# sx-wdec1-2313.net
KiCad netlist of a schematic drawn in EAGLE
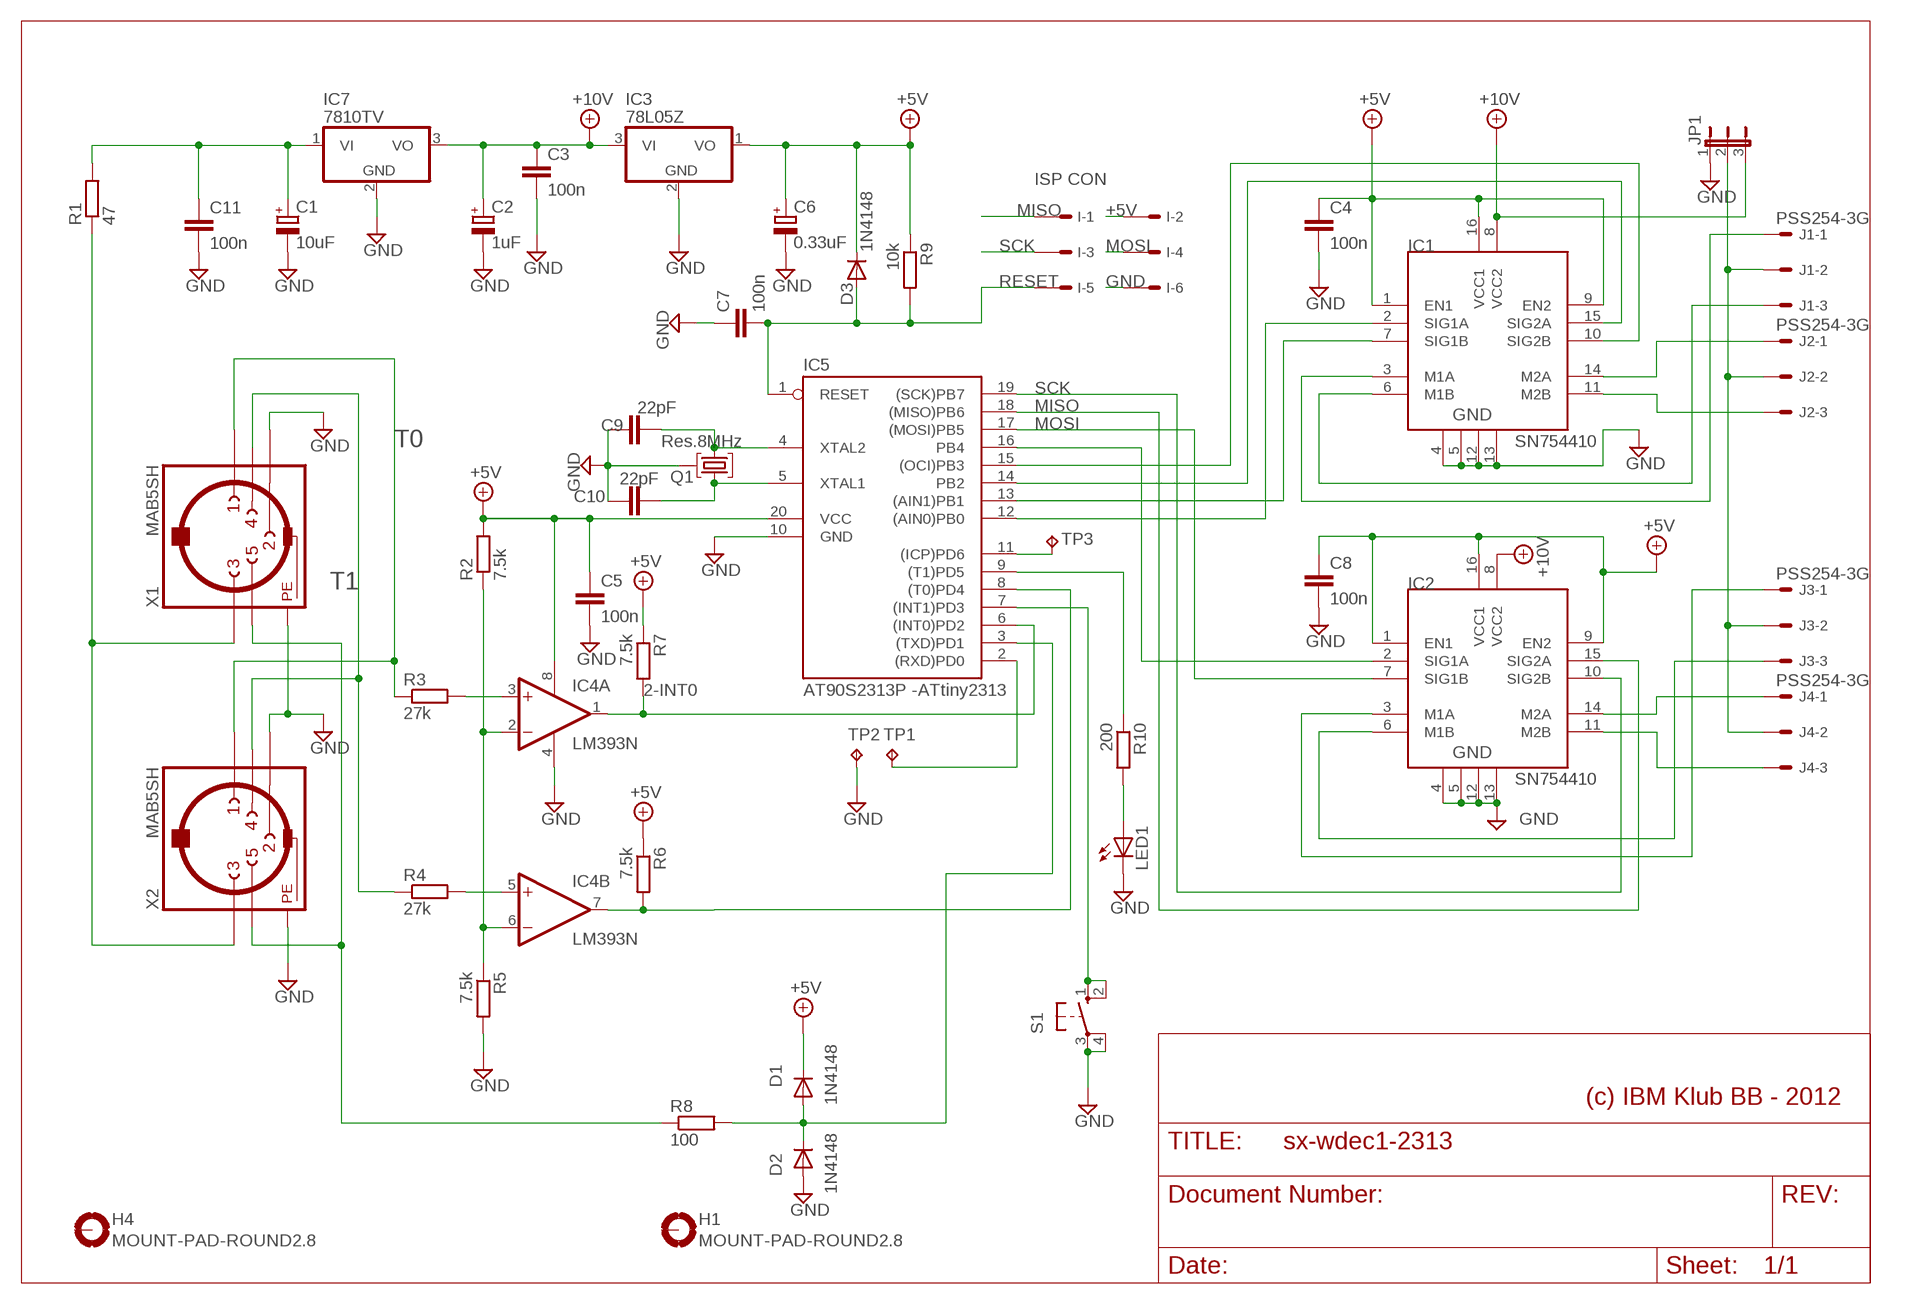
[diagram p0: schematic, sheet 1]

(export (version "E")
  (design (tool "Eeschema 10.0.6"))
  (components
    (comp (ref "C1")
      (value "10uF")
      (footprint "eagle-import:E2,5-7")
      (libsource (lib "eagle-import") (part "CPOL-EUE2.5-7"))
    )
    (comp (ref "C2")
      (value "1uF")
      (footprint "eagle-import:E2,5-7")
      (libsource (lib "eagle-import") (part "CPOL-EUE2.5-7"))
    )
    (comp (ref "C3")
      (value "100n")
      (footprint "eagle-import:C050-025X075")
      (libsource (lib "eagle-import") (part "C-EU050-025X075"))
    )
    (comp (ref "C4")
      (value "100n")
      (footprint "eagle-import:C050-025X075")
      (libsource (lib "eagle-import") (part "C-EU050-025X075"))
    )
    (comp (ref "C5")
      (value "100n")
      (footprint "eagle-import:C050-025X075")
      (libsource (lib "eagle-import") (part "C-EU050-025X075"))
    )
    (comp (ref "C6")
      (value "0.33uF")
      (footprint "eagle-import:E2,5-5")
      (libsource (lib "eagle-import") (part "CPOL-EUE2.5-5"))
    )
    (comp (ref "C7")
      (value "100n")
      (footprint "eagle-import:C050-025X075")
      (libsource (lib "eagle-import") (part "C-EU050-025X075"))
    )
    (comp (ref "C8")
      (value "100n")
      (footprint "eagle-import:C050-025X075")
      (libsource (lib "eagle-import") (part "C-EU050-025X075"))
    )
    (comp (ref "C9")
      (value "22pF")
      (footprint "eagle-import:C025-025X050")
      (libsource (lib "eagle-import") (part "C-EU025-025X050"))
    )
    (comp (ref "C10")
      (value "22pF")
      (footprint "eagle-import:C025-025X050")
      (libsource (lib "eagle-import") (part "C-EU025-025X050"))
    )
    (comp (ref "C11")
      (value "100n")
      (footprint "eagle-import:C050-025X075")
      (libsource (lib "eagle-import") (part "C-EU050-025X075"))
    )
    (comp (ref "D1")
      (value "1N4148")
      (footprint "eagle-import:DO35-7")
      (libsource (lib "eagle-import") (part "1N4148DO35-7"))
    )
    (comp (ref "D2")
      (value "1N4148")
      (footprint "eagle-import:DO35-7")
      (libsource (lib "eagle-import") (part "1N4148DO35-7"))
    )
    (comp (ref "D3")
      (value "1N4148")
      (footprint "eagle-import:DO35-7")
      (libsource (lib "eagle-import") (part "1N4148DO35-7"))
    )
    (comp (ref "H1")
      (value "MOUNT-PAD-ROUND2.8")
      (footprint "eagle-import:2,8-PAD")
      (libsource (lib "eagle-import") (part "MOUNT-PAD-ROUND2.8"))
    )
    (comp (ref "H4")
      (value "MOUNT-PAD-ROUND2.8")
      (footprint "eagle-import:2,8-PAD")
      (libsource (lib "eagle-import") (part "MOUNT-PAD-ROUND2.8"))
    )
    (comp (ref "I")
      (value "ISP CON")
      (footprint "eagle-import:057-006-1")
      (libsource (lib "eagle-import") (part "057-006-1"))
    )
    (comp (ref "IC1")
      (value "SN754410")
      (footprint "eagle-import:DIP16")
      (libsource (lib "eagle-import") (part "SN754410"))
    )
    (comp (ref "IC2")
      (value "SN754410")
      (footprint "eagle-import:DIP16")
      (libsource (lib "eagle-import") (part "SN754410"))
    )
    (comp (ref "IC3")
      (value "78L05Z")
      (footprint "eagle-import:TO92")
      (libsource (lib "eagle-import") (part "78ZL05"))
    )
    (comp (ref "IC4")
      (value "LM393N")
      (footprint "eagle-import:DIL08")
      (libsource (lib "eagle-import") (part "LM393N"))
    )
    (comp (ref "IC5")
      (value "AT90S2313P -ATtiny2313")
      (footprint "eagle-import:DIL20")
      (libsource (lib "eagle-import") (part "AT90S2313P"))
    )
    (comp (ref "IC7")
      (value "7810TV")
      (footprint "eagle-import:TO220V")
      (libsource (lib "eagle-import") (part "78TV12"))
    )
    (comp (ref "J1")
      (value "PSS254-3G")
      (footprint "eagle-import:6410-03")
      (libsource (lib "eagle-import") (part "22-?-0327-2031"))
    )
    (comp (ref "J2")
      (value "PSS254-3G")
      (footprint "eagle-import:6410-03")
      (libsource (lib "eagle-import") (part "22-?-0327-2031"))
    )
    (comp (ref "J3")
      (value "PSS254-3G")
      (footprint "eagle-import:6410-03")
      (libsource (lib "eagle-import") (part "22-?-0327-2031"))
    )
    (comp (ref "J4")
      (value "PSS254-3G")
      (footprint "eagle-import:6410-03")
      (libsource (lib "eagle-import") (part "22-?-0327-2031"))
    )
    (comp (ref "JP1")
      (value "JP2E")
      (footprint "eagle-import:JP2")
      (libsource (lib "eagle-import") (part "JP2E"))
    )
    (comp (ref "LED1")
      (value "LED3MM")
      (footprint "eagle-import:LED3MM")
      (libsource (lib "eagle-import") (part "LED3MM"))
    )
    (comp (ref "Q1")
      (value "Res.8MHz")
      (footprint "eagle-import:HC49U")
      (fields (field (name "OC_FARNELL") "unknown") (field (name "OC_NEWARK") "unknown"))
      (libsource (lib "eagle-import") (part "ECSECS-10.7-15A"))
    )
    (comp (ref "R1")
      (value "47")
      (footprint "eagle-import:0207_12")
      (libsource (lib "eagle-import") (part "R-EU_0207/12"))
    )
    (comp (ref "R2")
      (value "7.5k")
      (footprint "eagle-import:0207_10")
      (libsource (lib "eagle-import") (part "R-EU_0207/10"))
    )
    (comp (ref "R3")
      (value "27k")
      (footprint "eagle-import:0207_10")
      (libsource (lib "eagle-import") (part "R-EU_0207/10"))
    )
    (comp (ref "R4")
      (value "27k")
      (footprint "eagle-import:0207_10")
      (libsource (lib "eagle-import") (part "R-EU_0207/10"))
    )
    (comp (ref "R5")
      (value "7.5k")
      (footprint "eagle-import:0207_10")
      (libsource (lib "eagle-import") (part "R-EU_0207/10"))
    )
    (comp (ref "R6")
      (value "7.5k")
      (footprint "eagle-import:0207_10")
      (libsource (lib "eagle-import") (part "R-EU_0207/10"))
    )
    (comp (ref "R7")
      (value "7.5k")
      (footprint "eagle-import:0207_10")
      (libsource (lib "eagle-import") (part "R-EU_0207/10"))
    )
    (comp (ref "R8")
      (value "100")
      (footprint "eagle-import:0207_10")
      (libsource (lib "eagle-import") (part "R-EU_0207/10"))
    )
    (comp (ref "R9")
      (value "10k")
      (footprint "eagle-import:0207_10")
      (libsource (lib "eagle-import") (part "R-EU_0207/10"))
    )
    (comp (ref "R10")
      (value "200")
      (footprint "eagle-import:0207_10")
      (libsource (lib "eagle-import") (part "R-EU_0207/10"))
    )
    (comp (ref "S1")
      (value "10-XX")
      (footprint "eagle-import:B3F-10XX")
      (fields (field (name "MPN") "B3F-1000"))
      (libsource (lib "eagle-import") (part "10-XX"))
    )
    (comp (ref "TP1")
      (value "TPPAD1-13")
      (footprint "eagle-import:P1-13")
      (libsource (lib "eagle-import") (part "TPPAD1-13"))
    )
    (comp (ref "TP2")
      (value "TPPAD1-13")
      (footprint "eagle-import:P1-13")
      (libsource (lib "eagle-import") (part "TPPAD1-13"))
    )
    (comp (ref "TP3")
      (value "TPPAD1-13")
      (footprint "eagle-import:P1-13")
      (libsource (lib "eagle-import") (part "TPPAD1-13"))
    )
    (comp (ref "X1")
      (value "MAB5SH")
      (footprint "eagle-import:MAB5SH")
      (libsource (lib "eagle-import") (part "MAB5SH"))
    )
    (comp (ref "X2")
      (value "MAB5SH")
      (footprint "eagle-import:MAB5SH")
      (libsource (lib "eagle-import") (part "MAB5SH"))
    )
  )
  (nets
    (net (code "1") (name "+5V") (class "Default")
      (node (ref "C4") (pin "1") (pinfunction "1_1") (pintype "passive"))
      (node (ref "C5") (pin "1") (pinfunction "1_1") (pintype "passive"))
      (node (ref "C6") (pin "+") (pinfunction "+_+") (pintype "passive"))
      (node (ref "C8") (pin "1") (pinfunction "1_1") (pintype "passive"))
      (node (ref "D1") (pin "C") (pinfunction "C_C") (pintype "passive"))
      (node (ref "D3") (pin "C") (pinfunction "C_C") (pintype "passive"))
      (node (ref "I") (pin "2") (pinfunction "S_2") (pintype "passive"))
      (node (ref "IC1") (pin "1") (pinfunction "EN1_1") (pintype "bidirectional"))
      (node (ref "IC1") (pin "16") (pinfunction "VCC1_16") (pintype "power_in"))
      (node (ref "IC1") (pin "9") (pinfunction "EN2_9") (pintype "bidirectional"))
      (node (ref "IC2") (pin "1") (pinfunction "EN1_1") (pintype "bidirectional"))
      (node (ref "IC2") (pin "16") (pinfunction "VCC1_16") (pintype "power_in"))
      (node (ref "IC2") (pin "9") (pinfunction "EN2_9") (pintype "bidirectional"))
      (node (ref "IC3") (pin "1") (pinfunction "VO_1") (pintype "passive"))
      (node (ref "IC4") (pin "8") (pinfunction "V+_8") (pintype "power_in"))
      (node (ref "IC5") (pin "20") (pinfunction "VCC_20") (pintype "power_in"))
      (node (ref "R2") (pin "2") (pinfunction "2_2") (pintype "passive"))
      (node (ref "R6") (pin "1") (pinfunction "1_1") (pintype "passive"))
      (node (ref "R7") (pin "1") (pinfunction "1_1") (pintype "passive"))
      (node (ref "R9") (pin "1") (pinfunction "1_1") (pintype "passive"))
    )
    (net (code "2") (name "+10V") (class "Default")
      (node (ref "C2") (pin "+") (pinfunction "+_+") (pintype "passive"))
      (node (ref "C3") (pin "1") (pinfunction "1_1") (pintype "passive"))
      (node (ref "IC1") (pin "8") (pinfunction "VCC2_8") (pintype "power_in"))
      (node (ref "IC2") (pin "8") (pinfunction "VCC2_8") (pintype "power_in"))
      (node (ref "IC3") (pin "3") (pinfunction "VI_3") (pintype "input"))
      (node (ref "IC7") (pin "3") (pinfunction "VO_3") (pintype "passive"))
      (node (ref "JP1") (pin "3") (pinfunction "3_3") (pintype "passive"))
    )
    (net (code "3") (name "/2-INT0") (class "Default")
      (node (ref "IC4") (pin "1") (pinfunction "OUT_1") (pintype "output"))
      (node (ref "IC5") (pin "6") (pinfunction "(INT0)PD2_6") (pintype "bidirectional"))
      (node (ref "R7") (pin "2") (pinfunction "2_2") (pintype "passive"))
    )
    (net (code "4") (name "/MISO") (class "Default")
      (node (ref "I") (pin "1") (pinfunction "S_1") (pintype "passive"))
      (node (ref "IC2") (pin "15") (pinfunction "SIG2A_15") (pintype "bidirectional"))
      (node (ref "IC5") (pin "18") (pinfunction "(MISO)PB6_18") (pintype "bidirectional"))
    )
    (net (code "5") (name "/MOSI") (class "Default")
      (node (ref "I") (pin "4") (pinfunction "S_4") (pintype "passive"))
      (node (ref "IC2") (pin "7") (pinfunction "SIG1B_7") (pintype "bidirectional"))
      (node (ref "IC5") (pin "17") (pinfunction "(MOSI)PB5_17") (pintype "bidirectional"))
    )
    (net (code "6") (name "/RESET") (class "Default")
      (node (ref "C7") (pin "2") (pinfunction "2_2") (pintype "passive"))
      (node (ref "D3") (pin "A") (pinfunction "A_A") (pintype "passive"))
      (node (ref "I") (pin "5") (pinfunction "S_5") (pintype "passive"))
      (node (ref "IC5") (pin "1") (pinfunction "RESET_1") (pintype "bidirectional"))
      (node (ref "R9") (pin "2") (pinfunction "2_2") (pintype "passive"))
    )
    (net (code "7") (name "/SCK") (class "Default")
      (node (ref "I") (pin "3") (pinfunction "S_3") (pintype "passive"))
      (node (ref "IC2") (pin "10") (pinfunction "SIG2B_10") (pintype "bidirectional"))
      (node (ref "IC5") (pin "19") (pinfunction "(SCK)PB7_19") (pintype "bidirectional"))
    )
    (net (code "8") (name "/T0") (class "Default")
      (node (ref "R3") (pin "1") (pinfunction "1_1") (pintype "passive"))
      (node (ref "X1") (pin "1") (pinfunction "1_1") (pintype "passive"))
      (node (ref "X2") (pin "1") (pinfunction "1_1") (pintype "passive"))
    )
    (net (code "9") (name "/T1") (class "Default")
      (node (ref "R4") (pin "1") (pinfunction "1_1") (pintype "passive"))
      (node (ref "X1") (pin "4") (pinfunction "4_4") (pintype "passive"))
      (node (ref "X2") (pin "4") (pinfunction "4_4") (pintype "passive"))
    )
    (net (code "10") (name "GND") (class "Default")
      (node (ref "C1") (pin "-") (pinfunction "-_-") (pintype "passive"))
      (node (ref "C10") (pin "1") (pinfunction "1_1") (pintype "passive"))
      (node (ref "C11") (pin "2") (pinfunction "2_2") (pintype "passive"))
      (node (ref "C2") (pin "-") (pinfunction "-_-") (pintype "passive"))
      (node (ref "C3") (pin "2") (pinfunction "2_2") (pintype "passive"))
      (node (ref "C4") (pin "2") (pinfunction "2_2") (pintype "passive"))
      (node (ref "C5") (pin "2") (pinfunction "2_2") (pintype "passive"))
      (node (ref "C6") (pin "-") (pinfunction "-_-") (pintype "passive"))
      (node (ref "C7") (pin "1") (pinfunction "1_1") (pintype "passive"))
      (node (ref "C8") (pin "2") (pinfunction "2_2") (pintype "passive"))
      (node (ref "C9") (pin "1") (pinfunction "1_1") (pintype "passive"))
      (node (ref "D2") (pin "A") (pinfunction "A_A") (pintype "passive"))
      (node (ref "I") (pin "6") (pinfunction "S_6") (pintype "passive"))
      (node (ref "IC1") (pin "12") (pinfunction "P12_12") (pintype "power_in"))
      (node (ref "IC1") (pin "13") (pinfunction "P13_13") (pintype "power_in"))
      (node (ref "IC1") (pin "4") (pinfunction "P4_4") (pintype "power_in"))
      (node (ref "IC1") (pin "5") (pinfunction "P5_5") (pintype "power_in"))
      (node (ref "IC2") (pin "12") (pinfunction "P12_12") (pintype "power_in"))
      (node (ref "IC2") (pin "13") (pinfunction "P13_13") (pintype "power_in"))
      (node (ref "IC2") (pin "4") (pinfunction "P4_4") (pintype "power_in"))
      (node (ref "IC2") (pin "5") (pinfunction "P5_5") (pintype "power_in"))
      (node (ref "IC3") (pin "2") (pinfunction "GND_2") (pintype "passive"))
      (node (ref "IC4") (pin "4") (pinfunction "V-_4") (pintype "power_in"))
      (node (ref "IC5") (pin "10") (pinfunction "GND_10") (pintype "power_in"))
      (node (ref "IC7") (pin "2") (pinfunction "GND_2") (pintype "passive"))
      (node (ref "JP1") (pin "1") (pinfunction "1_1") (pintype "passive"))
      (node (ref "LED1") (pin "K") (pinfunction "C_K") (pintype "passive"))
      (node (ref "Q1") (pin "2") (pinfunction "2_2") (pintype "passive"))
      (node (ref "R5") (pin "2") (pinfunction "2_2") (pintype "passive"))
      (node (ref "S1") (pin "3") (pinfunction "P_3") (pintype "passive"))
      (node (ref "S1") (pin "4") (pinfunction "P1_4") (pintype "passive"))
      (node (ref "TP2") (pin "TP") (pinfunction "TP_TP") (pintype "input"))
      (node (ref "X1") (pin "2") (pinfunction "2_2") (pintype "passive"))
      (node (ref "X1") (pin "PE") (pinfunction "PE_PE") (pintype "power_in"))
      (node (ref "X1") (pin "PE@") (pinfunction "PE_PE@") (pintype "power_in"))
      (node (ref "X2") (pin "2") (pinfunction "2_2") (pintype "passive"))
      (node (ref "X2") (pin "PE") (pinfunction "PE_PE") (pintype "power_in"))
      (node (ref "X2") (pin "PE@") (pinfunction "PE_PE@") (pintype "power_in"))
    )
    (net (code "11") (name "Net-(IC1-M1A)") (class "Default")
      (node (ref "IC1") (pin "3") (pinfunction "M1A_3") (pintype "bidirectional"))
      (node (ref "J1") (pin "1") (pinfunction "S_1") (pintype "passive"))
    )
    (net (code "12") (name "Net-(IC1-M1B)") (class "Default")
      (node (ref "IC1") (pin "6") (pinfunction "M1B_6") (pintype "bidirectional"))
      (node (ref "J1") (pin "3") (pinfunction "S_3") (pintype "passive"))
    )
    (net (code "13") (name "Net-(IC1-M2A)") (class "Default")
      (node (ref "IC1") (pin "14") (pinfunction "M2A_14") (pintype "bidirectional"))
      (node (ref "J2") (pin "1") (pinfunction "S_1") (pintype "passive"))
    )
    (net (code "14") (name "Net-(IC1-M2B)") (class "Default")
      (node (ref "IC1") (pin "11") (pinfunction "M2B_11") (pintype "bidirectional"))
      (node (ref "J2") (pin "3") (pinfunction "S_3") (pintype "passive"))
    )
    (net (code "15") (name "Net-(IC1-SIG1A)") (class "Default")
      (node (ref "IC1") (pin "2") (pinfunction "SIG1A_2") (pintype "bidirectional"))
      (node (ref "IC5") (pin "12") (pinfunction "(AIN0)PB0_12") (pintype "bidirectional"))
    )
    (net (code "16") (name "Net-(IC1-SIG1B)") (class "Default")
      (node (ref "IC1") (pin "7") (pinfunction "SIG1B_7") (pintype "bidirectional"))
      (node (ref "IC5") (pin "13") (pinfunction "(AIN1)PB1_13") (pintype "bidirectional"))
    )
    (net (code "17") (name "Net-(IC1-SIG2A)") (class "Default")
      (node (ref "IC1") (pin "15") (pinfunction "SIG2A_15") (pintype "bidirectional"))
      (node (ref "IC5") (pin "14") (pinfunction "PB2_14") (pintype "bidirectional"))
    )
    (net (code "18") (name "Net-(IC1-SIG2B)") (class "Default")
      (node (ref "IC1") (pin "10") (pinfunction "SIG2B_10") (pintype "bidirectional"))
      (node (ref "IC5") (pin "15") (pinfunction "(OCI)PB3_15") (pintype "bidirectional"))
    )
    (net (code "19") (name "Net-(IC2-M1A)") (class "Default")
      (node (ref "IC2") (pin "3") (pinfunction "M1A_3") (pintype "bidirectional"))
      (node (ref "J3") (pin "1") (pinfunction "S_1") (pintype "passive"))
    )
    (net (code "20") (name "Net-(IC2-M1B)") (class "Default")
      (node (ref "IC2") (pin "6") (pinfunction "M1B_6") (pintype "bidirectional"))
      (node (ref "J3") (pin "3") (pinfunction "S_3") (pintype "passive"))
    )
    (net (code "21") (name "Net-(IC2-M2A)") (class "Default")
      (node (ref "IC2") (pin "14") (pinfunction "M2A_14") (pintype "bidirectional"))
      (node (ref "J4") (pin "1") (pinfunction "S_1") (pintype "passive"))
    )
    (net (code "22") (name "Net-(IC2-M2B)") (class "Default")
      (node (ref "IC2") (pin "11") (pinfunction "M2B_11") (pintype "bidirectional"))
      (node (ref "J4") (pin "3") (pinfunction "S_3") (pintype "passive"))
    )
    (net (code "23") (name "Net-(IC2-SIG1A)") (class "Default")
      (node (ref "IC2") (pin "2") (pinfunction "SIG1A_2") (pintype "bidirectional"))
      (node (ref "IC5") (pin "16") (pinfunction "PB4_16") (pintype "bidirectional"))
    )
    (net (code "24") (name "Net-(IC4A-+IN)") (class "Default")
      (node (ref "IC4") (pin "3") (pinfunction "+IN_3") (pintype "input"))
      (node (ref "R3") (pin "2") (pinfunction "2_2") (pintype "passive"))
    )
    (net (code "25") (name "Net-(IC4A--IN)") (class "Default")
      (node (ref "IC4") (pin "2") (pinfunction "-IN_2") (pintype "input"))
      (node (ref "IC4") (pin "6") (pinfunction "-IN_6") (pintype "input"))
      (node (ref "R2") (pin "1") (pinfunction "1_1") (pintype "passive"))
      (node (ref "R5") (pin "1") (pinfunction "1_1") (pintype "passive"))
    )
    (net (code "26") (name "Net-(IC4B-+IN)") (class "Default")
      (node (ref "IC4") (pin "5") (pinfunction "+IN_5") (pintype "input"))
      (node (ref "R4") (pin "2") (pinfunction "2_2") (pintype "passive"))
    )
    (net (code "27") (name "Net-(IC4B-OUT)") (class "Default")
      (node (ref "IC4") (pin "7") (pinfunction "OUT_7") (pintype "output"))
      (node (ref "IC5") (pin "8") (pinfunction "(T0)PD4_8") (pintype "bidirectional"))
      (node (ref "R6") (pin "2") (pinfunction "2_2") (pintype "passive"))
    )
    (net (code "28") (name "Net-(IC5-(ICP)PD6)") (class "Default")
      (node (ref "IC5") (pin "11") (pinfunction "(ICP)PD6_11") (pintype "bidirectional"))
      (node (ref "TP3") (pin "TP") (pinfunction "TP_TP") (pintype "input"))
    )
    (net (code "29") (name "Net-(IC5-(INT1)PD3)") (class "Default")
      (node (ref "IC5") (pin "7") (pinfunction "(INT1)PD3_7") (pintype "bidirectional"))
      (node (ref "S1") (pin "1") (pinfunction "S_1") (pintype "passive"))
      (node (ref "S1") (pin "2") (pinfunction "S1_2") (pintype "passive"))
    )
    (net (code "30") (name "Net-(IC5-(RXD)PD0)") (class "Default")
      (node (ref "IC5") (pin "2") (pinfunction "(RXD)PD0_2") (pintype "bidirectional"))
      (node (ref "TP1") (pin "TP") (pinfunction "TP_TP") (pintype "input"))
    )
    (net (code "31") (name "Net-(IC5-(T1)PD5)") (class "Default")
      (node (ref "IC5") (pin "9") (pinfunction "(T1)PD5_9") (pintype "bidirectional"))
      (node (ref "R10") (pin "1") (pinfunction "1_1") (pintype "passive"))
    )
    (net (code "32") (name "Net-(IC5-(TXD)PD1)") (class "Default")
      (node (ref "D1") (pin "A") (pinfunction "A_A") (pintype "passive"))
      (node (ref "D2") (pin "C") (pinfunction "C_C") (pintype "passive"))
      (node (ref "IC5") (pin "3") (pinfunction "(TXD)PD1_3") (pintype "bidirectional"))
      (node (ref "R8") (pin "2") (pinfunction "2_2") (pintype "passive"))
    )
    (net (code "33") (name "Net-(IC5-XTAL1)") (class "Default")
      (node (ref "C10") (pin "2") (pinfunction "2_2") (pintype "passive"))
      (node (ref "IC5") (pin "5") (pinfunction "XTAL1_5") (pintype "bidirectional"))
      (node (ref "Q1") (pin "3") (pinfunction "3_3") (pintype "passive"))
    )
    (net (code "34") (name "Net-(IC5-XTAL2)") (class "Default")
      (node (ref "C9") (pin "2") (pinfunction "2_2") (pintype "passive"))
      (node (ref "IC5") (pin "4") (pinfunction "XTAL2_4") (pintype "bidirectional"))
      (node (ref "Q1") (pin "1") (pinfunction "1_1") (pintype "passive"))
    )
    (net (code "35") (name "Net-(IC7-VI)") (class "Default")
      (node (ref "C1") (pin "+") (pinfunction "+_+") (pintype "passive"))
      (node (ref "C11") (pin "1") (pinfunction "1_1") (pintype "passive"))
      (node (ref "IC7") (pin "1") (pinfunction "VI_1") (pintype "input"))
      (node (ref "R1") (pin "2") (pinfunction "2_2") (pintype "passive"))
    )
    (net (code "36") (name "Net-(J1B-S)") (class "Default")
      (node (ref "J1") (pin "2") (pinfunction "S_2") (pintype "passive"))
      (node (ref "J2") (pin "2") (pinfunction "S_2") (pintype "passive"))
      (node (ref "J3") (pin "2") (pinfunction "S_2") (pintype "passive"))
      (node (ref "J4") (pin "2") (pinfunction "S_2") (pintype "passive"))
      (node (ref "JP1") (pin "2") (pinfunction "2_2") (pintype "passive"))
    )
    (net (code "37") (name "Net-(LED1-PadA)") (class "Default")
      (node (ref "LED1") (pin "A") (pinfunction "A_A") (pintype "passive"))
      (node (ref "R10") (pin "2") (pinfunction "2_2") (pintype "passive"))
    )
    (net (code "38") (name "Net-(R1-Pad1)") (class "Default")
      (node (ref "R1") (pin "1") (pinfunction "1_1") (pintype "passive"))
      (node (ref "X1") (pin "3") (pinfunction "3_3") (pintype "passive"))
      (node (ref "X2") (pin "3") (pinfunction "3_3") (pintype "passive"))
    )
    (net (code "39") (name "Net-(R8-Pad1)") (class "Default")
      (node (ref "R8") (pin "1") (pinfunction "1_1") (pintype "passive"))
      (node (ref "X1") (pin "5") (pinfunction "5_5") (pintype "passive"))
      (node (ref "X2") (pin "5") (pinfunction "5_5") (pintype "passive"))
    )
    (net (code "40") (name "unconnected-(H1-MOUNT-PadB2,8)") (class "Default")
      (node (ref "H1") (pin "B2,8") (pinfunction "MOUNT_B2,8") (pintype "passive"))
    )
    (net (code "41") (name "unconnected-(H4-MOUNT-PadB2,8)") (class "Default")
      (node (ref "H4") (pin "B2,8") (pinfunction "MOUNT_B2,8") (pintype "passive"))
    )
  )
)
